# 3_INTERFACE_DOS_DRIVERS.net
KiCad netlist of a schematic drawn in Altium Designer
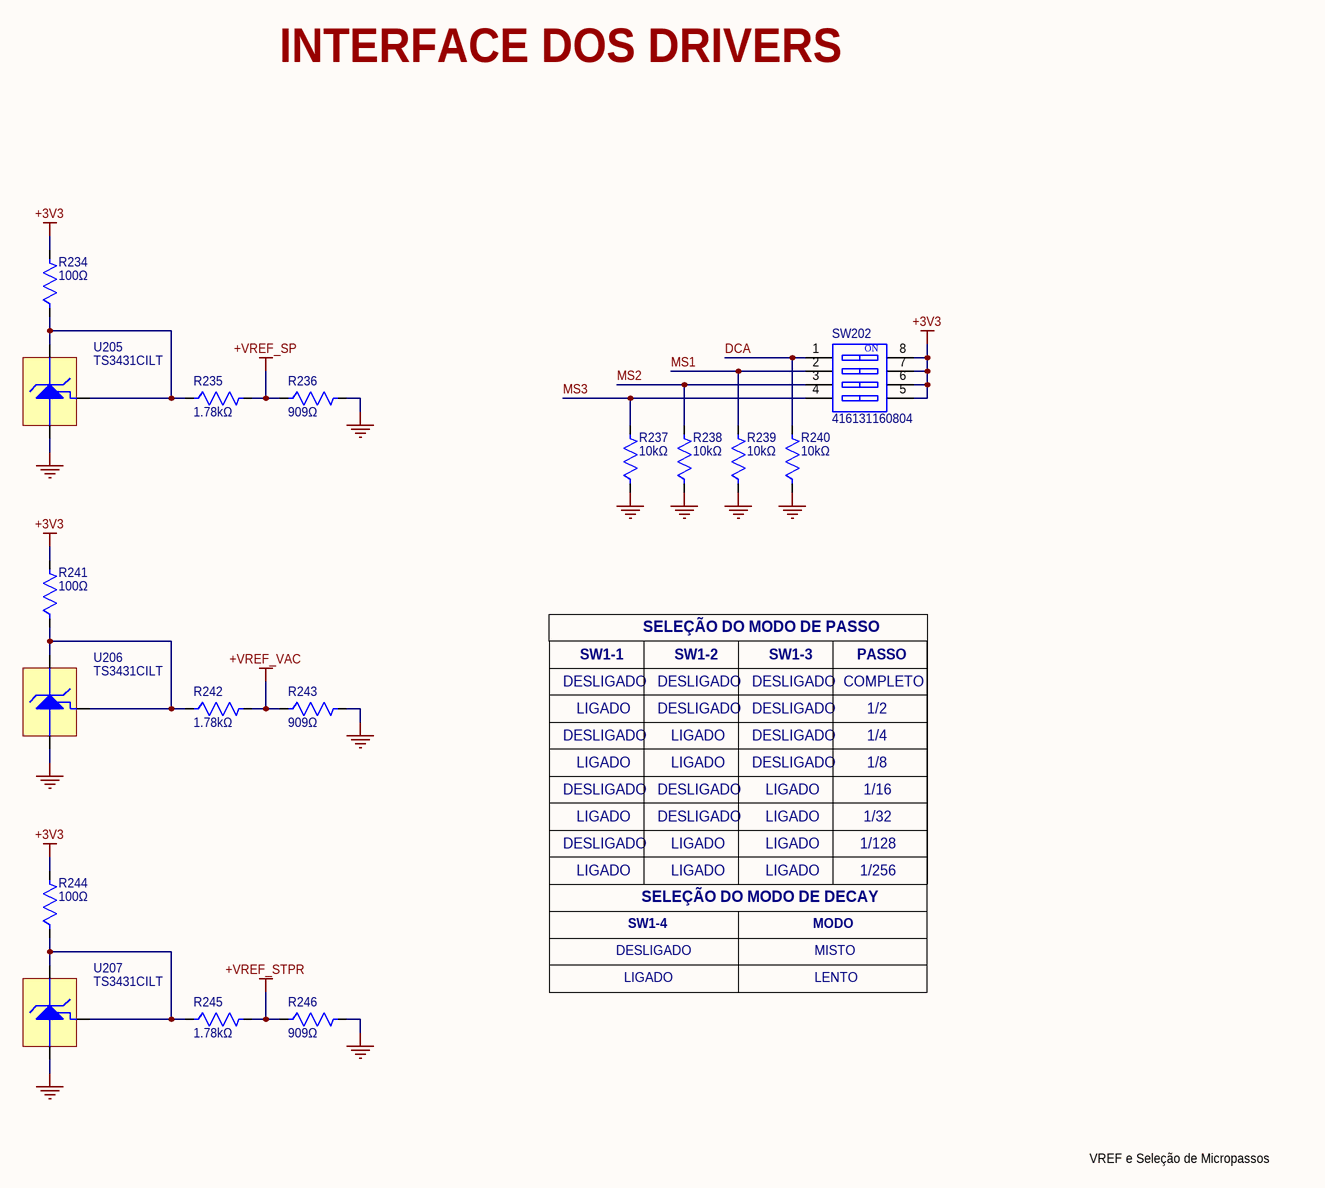
[diagram p0: 3_INTERFACE_DOS_DRIVERS.SchDoc]

(export (version "E")
  (design (tool "Eeschema 10.0.6"))
  (components
    (comp (ref "R234")
      (value "100Ω")
      (footprint "0603-WAVE")
      (description "RES 100 OHM 1% 1/10W 0603")
      (fields
        (field (name "MANUFACTURER PART NUMBER") "RC0603FR-07100RL")
        (field (name "MANUFACTURER") "Yageo Group")
      )
      (libsource (lib "Resistors-0603-E96-Yageo") (part "RC0603FR-07100RL"))
    )
    (comp (ref "R235")
      (value "1.78kΩ")
      (footprint "0603-WAVE")
      (description "RES 1.78K OHM 1% 1/10W 0603")
      (fields
        (field (name "MANUFACTURER PART NUMBER") "RC0603FR-071K78L")
        (field (name "MANUFACTURER") "Yageo Group")
      )
      (libsource (lib "Resistors-0603-E96-Yageo") (part "RC0603FR-071K78L"))
    )
    (comp (ref "R236")
      (value "909Ω")
      (footprint "0603-WAVE")
      (description "RES 909 OHM 1% 1/10W 0603")
      (fields
        (field (name "MANUFACTURER PART NUMBER") "RC0603FR-07909RL")
        (field (name "MANUFACTURER") "Yageo Group")
      )
      (libsource (lib "Resistors-0603-E96-Yageo") (part "RC0603FR-07909RL"))
    )
    (comp (ref "R237")
      (value "10kΩ")
      (footprint "0603-WAVE")
      (description "RES 10K OHM 1% 1/10W 0603")
      (fields
        (field (name "MANUFACTURER PART NUMBER") "RC0603FR-0710KL")
        (field (name "MANUFACTURER") "Yageo Group")
      )
      (libsource (lib "Resistors-0603-E96-Yageo") (part "RC0603FR-0710KL"))
    )
    (comp (ref "R238")
      (value "10kΩ")
      (footprint "0603-WAVE")
      (description "RES 10K OHM 1% 1/10W 0603")
      (fields
        (field (name "MANUFACTURER PART NUMBER") "RC0603FR-0710KL")
        (field (name "MANUFACTURER") "Yageo Group")
      )
      (libsource (lib "Resistors-0603-E96-Yageo") (part "RC0603FR-0710KL"))
    )
    (comp (ref "R239")
      (value "10kΩ")
      (footprint "0603-WAVE")
      (description "RES 10K OHM 1% 1/10W 0603")
      (fields
        (field (name "MANUFACTURER PART NUMBER") "RC0603FR-0710KL")
        (field (name "MANUFACTURER") "Yageo Group")
      )
      (libsource (lib "Resistors-0603-E96-Yageo") (part "RC0603FR-0710KL"))
    )
    (comp (ref "R240")
      (value "10kΩ")
      (footprint "0603-WAVE")
      (description "RES 10K OHM 1% 1/10W 0603")
      (fields
        (field (name "MANUFACTURER PART NUMBER") "RC0603FR-0710KL")
        (field (name "MANUFACTURER") "Yageo Group")
      )
      (libsource (lib "Resistors-0603-E96-Yageo") (part "RC0603FR-0710KL"))
    )
    (comp (ref "R241")
      (value "100Ω")
      (footprint "0603-WAVE")
      (description "RES 100 OHM 1% 1/10W 0603")
      (fields
        (field (name "MANUFACTURER PART NUMBER") "RC0603FR-07100RL")
        (field (name "MANUFACTURER") "Yageo Group")
      )
      (libsource (lib "Resistors-0603-E96-Yageo") (part "RC0603FR-07100RL"))
    )
    (comp (ref "R242")
      (value "1.78kΩ")
      (footprint "0603-WAVE")
      (description "RES 1.78K OHM 1% 1/10W 0603")
      (fields
        (field (name "MANUFACTURER PART NUMBER") "RC0603FR-071K78L")
        (field (name "MANUFACTURER") "Yageo Group")
      )
      (libsource (lib "Resistors-0603-E96-Yageo") (part "RC0603FR-071K78L"))
    )
    (comp (ref "R243")
      (value "909Ω")
      (footprint "0603-WAVE")
      (description "RES 909 OHM 1% 1/10W 0603")
      (fields
        (field (name "MANUFACTURER PART NUMBER") "RC0603FR-07909RL")
        (field (name "MANUFACTURER") "Yageo Group")
      )
      (libsource (lib "Resistors-0603-E96-Yageo") (part "RC0603FR-07909RL"))
    )
    (comp (ref "R244")
      (value "100Ω")
      (footprint "0603-WAVE")
      (description "RES 100 OHM 1% 1/10W 0603")
      (fields
        (field (name "MANUFACTURER PART NUMBER") "RC0603FR-07100RL")
        (field (name "MANUFACTURER") "Yageo Group")
      )
      (libsource (lib "Resistors-0603-E96-Yageo") (part "RC0603FR-07100RL"))
    )
    (comp (ref "R245")
      (value "1.78kΩ")
      (footprint "0603-WAVE")
      (description "RES 1.78K OHM 1% 1/10W 0603")
      (fields
        (field (name "MANUFACTURER PART NUMBER") "RC0603FR-071K78L")
        (field (name "MANUFACTURER") "Yageo Group")
      )
      (libsource (lib "Resistors-0603-E96-Yageo") (part "RC0603FR-071K78L"))
    )
    (comp (ref "R246")
      (value "909Ω")
      (footprint "0603-WAVE")
      (description "RES 909 OHM 1% 1/10W 0603")
      (fields
        (field (name "MANUFACTURER PART NUMBER") "RC0603FR-07909RL")
        (field (name "MANUFACTURER") "Yageo Group")
      )
      (libsource (lib "Resistors-0603-E96-Yageo") (part "RC0603FR-07909RL"))
    )
    (comp (ref "SW202")
      (value "416131160804")
      (footprint "416131160804")
      (description "WS-DISV Small Compact SMD Dip Switch, Flat Actuator with Top Tape, pitch 1.27mm, 4p")
      (fields (field (name "MANUFACTURER") "Wurth Elektronik"))
      (libsource (lib "WE - Electromechanical Components") (part "DIP-4"))
    )
    (comp (ref "U205")
      (value "TS3431CILT")
      (footprint "SOT-23-3")
      (description "IC VREF SHUNT ADJ 0.25% SOT23-3")
      (fields (field (name "MANUFACTURER") "STMicroelectronics") (field (name "TOLERANCE") "0.25%"))
      (libsource (lib "Voltage-Reference") (part "TS3431CILT"))
    )
    (comp (ref "U206")
      (value "TS3431CILT")
      (footprint "SOT-23-3")
      (description "IC VREF SHUNT ADJ 0.25% SOT23-3")
      (fields (field (name "MANUFACTURER") "STMicroelectronics") (field (name "TOLERANCE") "0.25%"))
      (libsource (lib "Voltage-Reference") (part "TS3431CILT"))
    )
    (comp (ref "U207")
      (value "TS3431CILT")
      (footprint "SOT-23-3")
      (description "IC VREF SHUNT ADJ 0.25% SOT23-3")
      (fields (field (name "MANUFACTURER") "STMicroelectronics") (field (name "TOLERANCE") "0.25%"))
      (libsource (lib "Voltage-Reference") (part "TS3431CILT"))
    )
  )
  (nets
    (net (code "1") (name "+3V3") (class "Default")
      (node (ref "R234") (pin "2") (pinfunction "2_2") (pintype "passive"))
      (node (ref "R241") (pin "2") (pinfunction "2_2") (pintype "passive"))
      (node (ref "R244") (pin "2") (pinfunction "2_2") (pintype "passive"))
      (node (ref "SW202") (pin "5") (pinfunction "5_5") (pintype "passive"))
      (node (ref "SW202") (pin "6") (pinfunction "6_6") (pintype "passive"))
      (node (ref "SW202") (pin "7") (pinfunction "7_7") (pintype "passive"))
      (node (ref "SW202") (pin "8") (pinfunction "8_8") (pintype "passive"))
    )
    (net (code "2") (name "+VREF_SP") (class "Default")
      (node (ref "R235") (pin "2") (pinfunction "2_2") (pintype "passive"))
      (node (ref "R236") (pin "1") (pinfunction "1_1") (pintype "passive"))
    )
    (net (code "3") (name "+VREF_STPR") (class "Default")
      (node (ref "R245") (pin "2") (pinfunction "2_2") (pintype "passive"))
      (node (ref "R246") (pin "1") (pinfunction "1_1") (pintype "passive"))
    )
    (net (code "4") (name "+VREF_VAC") (class "Default")
      (node (ref "R242") (pin "2") (pinfunction "2_2") (pintype "passive"))
      (node (ref "R243") (pin "1") (pinfunction "1_1") (pintype "passive"))
    )
    (net (code "5") (name "/DCA") (class "Default")
      (node (ref "R240") (pin "2") (pinfunction "2_2") (pintype "passive"))
      (node (ref "SW202") (pin "1") (pinfunction "1_1") (pintype "passive"))
    )
    (net (code "6") (name "/MS1") (class "Default")
      (node (ref "R239") (pin "2") (pinfunction "2_2") (pintype "passive"))
      (node (ref "SW202") (pin "2") (pinfunction "2_2") (pintype "passive"))
    )
    (net (code "7") (name "/MS2") (class "Default")
      (node (ref "R238") (pin "2") (pinfunction "2_2") (pintype "passive"))
      (node (ref "SW202") (pin "3") (pinfunction "3_3") (pintype "passive"))
    )
    (net (code "8") (name "/MS3") (class "Default")
      (node (ref "R237") (pin "2") (pinfunction "2_2") (pintype "passive"))
      (node (ref "SW202") (pin "4") (pinfunction "4_4") (pintype "passive"))
    )
    (net (code "9") (name "GND") (class "Default")
      (node (ref "R236") (pin "2") (pinfunction "2_2") (pintype "passive"))
      (node (ref "R237") (pin "1") (pinfunction "1_1") (pintype "passive"))
      (node (ref "R238") (pin "1") (pinfunction "1_1") (pintype "passive"))
      (node (ref "R239") (pin "1") (pinfunction "1_1") (pintype "passive"))
      (node (ref "R240") (pin "1") (pinfunction "1_1") (pintype "passive"))
      (node (ref "R243") (pin "2") (pinfunction "2_2") (pintype "passive"))
      (node (ref "R246") (pin "2") (pinfunction "2_2") (pintype "passive"))
      (node (ref "U205") (pin "3") (pinfunction "ANODE_3") (pintype "passive"))
      (node (ref "U206") (pin "3") (pinfunction "ANODE_3") (pintype "passive"))
      (node (ref "U207") (pin "3") (pinfunction "ANODE_3") (pintype "passive"))
    )
    (net (code "10") (name "Net-(U205-CATHODE)") (class "Default")
      (node (ref "R234") (pin "1") (pinfunction "1_1") (pintype "passive"))
      (node (ref "R235") (pin "1") (pinfunction "1_1") (pintype "passive"))
      (node (ref "U205") (pin "1") (pinfunction "REF_1") (pintype "passive"))
      (node (ref "U205") (pin "2") (pinfunction "CATHODE_2") (pintype "passive"))
    )
    (net (code "11") (name "Net-(U206-CATHODE)") (class "Default")
      (node (ref "R241") (pin "1") (pinfunction "1_1") (pintype "passive"))
      (node (ref "R242") (pin "1") (pinfunction "1_1") (pintype "passive"))
      (node (ref "U206") (pin "1") (pinfunction "REF_1") (pintype "passive"))
      (node (ref "U206") (pin "2") (pinfunction "CATHODE_2") (pintype "passive"))
    )
    (net (code "12") (name "Net-(U207-CATHODE)") (class "Default")
      (node (ref "R244") (pin "1") (pinfunction "1_1") (pintype "passive"))
      (node (ref "R245") (pin "1") (pinfunction "1_1") (pintype "passive"))
      (node (ref "U207") (pin "1") (pinfunction "REF_1") (pintype "passive"))
      (node (ref "U207") (pin "2") (pinfunction "CATHODE_2") (pintype "passive"))
    )
  )
)
